# IR-Receiver.net
KiCad netlist of a schematic drawn in EAGLE
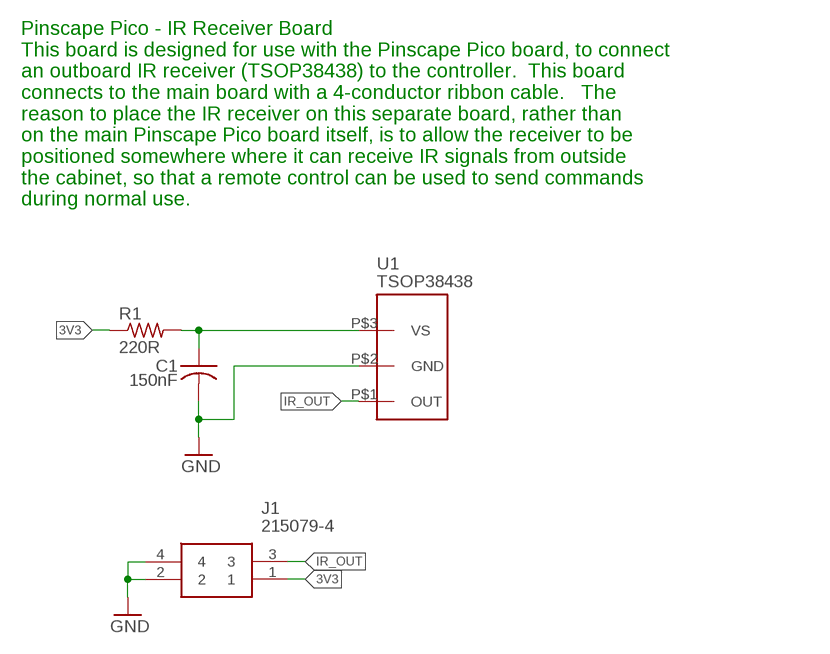
[diagram p0: schematic, sheet 1]

(export (version "E")
  (design (tool "Eeschema 10.0.6"))
  (components
    (comp (ref "C1")
      (value "150nF")
      (footprint "eagle-import:C025-040X050")
      (libsource (lib "eagle-import") (part "C-US025-040X050"))
    )
    (comp (ref "J1")
      (value "215079-4")
      (footprint "eagle-import:2150794")
      (fields (field (name "MOUSER_PART_NUMBER") "571-215079-4"))
      (libsource (lib "eagle-import") (part "215079-4"))
    )
    (comp (ref "R1")
      (value "220R")
      (footprint "eagle-import:0204_7")
      (fields (field (name "PARTNO") "660-MS1/4DCT52R1002"))
      (libsource (lib "eagle-import") (part "R-US_0204/7"))
    )
    (comp (ref "U1")
      (value "TSOP38438")
      (footprint "eagle-import:TSOP382")
      (libsource (lib "eagle-import") (part "TSOP382"))
    )
  )
  (nets
    (net (code "1") (name "3V3") (class "Default")
      (node (ref "J1") (pin "1") (pinfunction "1_1") (pintype "bidirectional"))
      (node (ref "R1") (pin "1") (pinfunction "1_1") (pintype "passive"))
    )
    (net (code "2") (name "GND") (class "Default")
      (node (ref "C1") (pin "2") (pinfunction "2_2") (pintype "passive"))
      (node (ref "J1") (pin "2") (pinfunction "2_2") (pintype "bidirectional"))
      (node (ref "J1") (pin "4") (pinfunction "4_4") (pintype "bidirectional"))
      (node (ref "U1") (pin "P$2") (pinfunction "GND_P$2") (pintype "power_in"))
    )
    (net (code "3") (name "IR_OUT") (class "Default")
      (node (ref "J1") (pin "3") (pinfunction "3_3") (pintype "bidirectional"))
      (node (ref "U1") (pin "P$1") (pinfunction "OUT_P$1") (pintype "output"))
    )
    (net (code "4") (name "Net-(U1-VS)") (class "Default")
      (node (ref "C1") (pin "1") (pinfunction "1_1") (pintype "passive"))
      (node (ref "R1") (pin "2") (pinfunction "2_2") (pintype "passive"))
      (node (ref "U1") (pin "P$3") (pinfunction "VS_P$3") (pintype "power_in"))
    )
  )
)
